# PSU_1084SET_2V5.net
KiCad netlist of a schematic drawn in Altium Designer
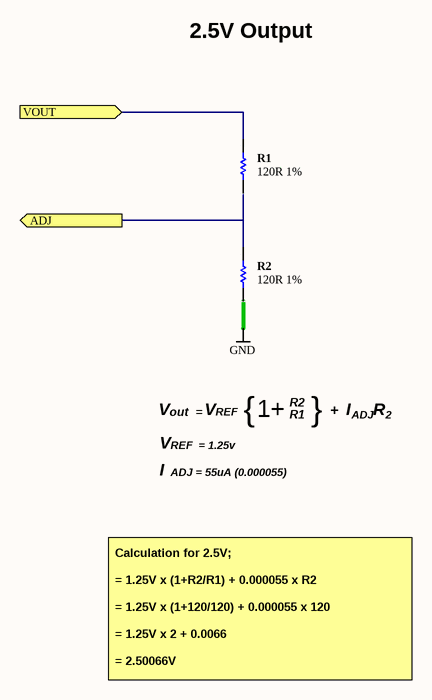
[diagram p0: PSU_1084SET_2V5.SchDoc]

(export (version "E")
  (design (tool "Eeschema 10.0.6"))
  (components
    (comp (ref "R1")
      (value "120R 1%")
      (footprint "RESC1005-STAR")
      (description "Resistor, 120R 1% 0402 (1005)")
      (fields (field (name "TOLERANCE") "1 %"))
      (libsource (lib "AltiumDesignLibrary") (part "RES"))
    )
    (comp (ref "R2")
      (value "120R 1%")
      (footprint "RESC1005-STAR")
      (description "Resistor, 120R 1% 0402 (1005)")
      (fields (field (name "TOLERANCE") "1 %"))
      (libsource (lib "AltiumDesignLibrary") (part "RES"))
    )
  )
  (nets
    (net (code "1") (name "/ADJ") (class "Default")
      (node (ref "R1") (pin "1") (pinfunction "1_1") (pintype "passive"))
      (node (ref "R2") (pin "1") (pinfunction "1_1") (pintype "passive"))
    )
    (net (code "2") (name "/VOUT") (class "Default")
      (node (ref "R1") (pin "2") (pinfunction "2_2") (pintype "passive"))
    )
    (net (code "3") (name "GND") (class "Default")
      (node (ref "R2") (pin "2") (pinfunction "2_2") (pintype "passive"))
    )
  )
)
